# trinketm0fader_35mmad.net
KiCad netlist of a schematic drawn in EAGLE
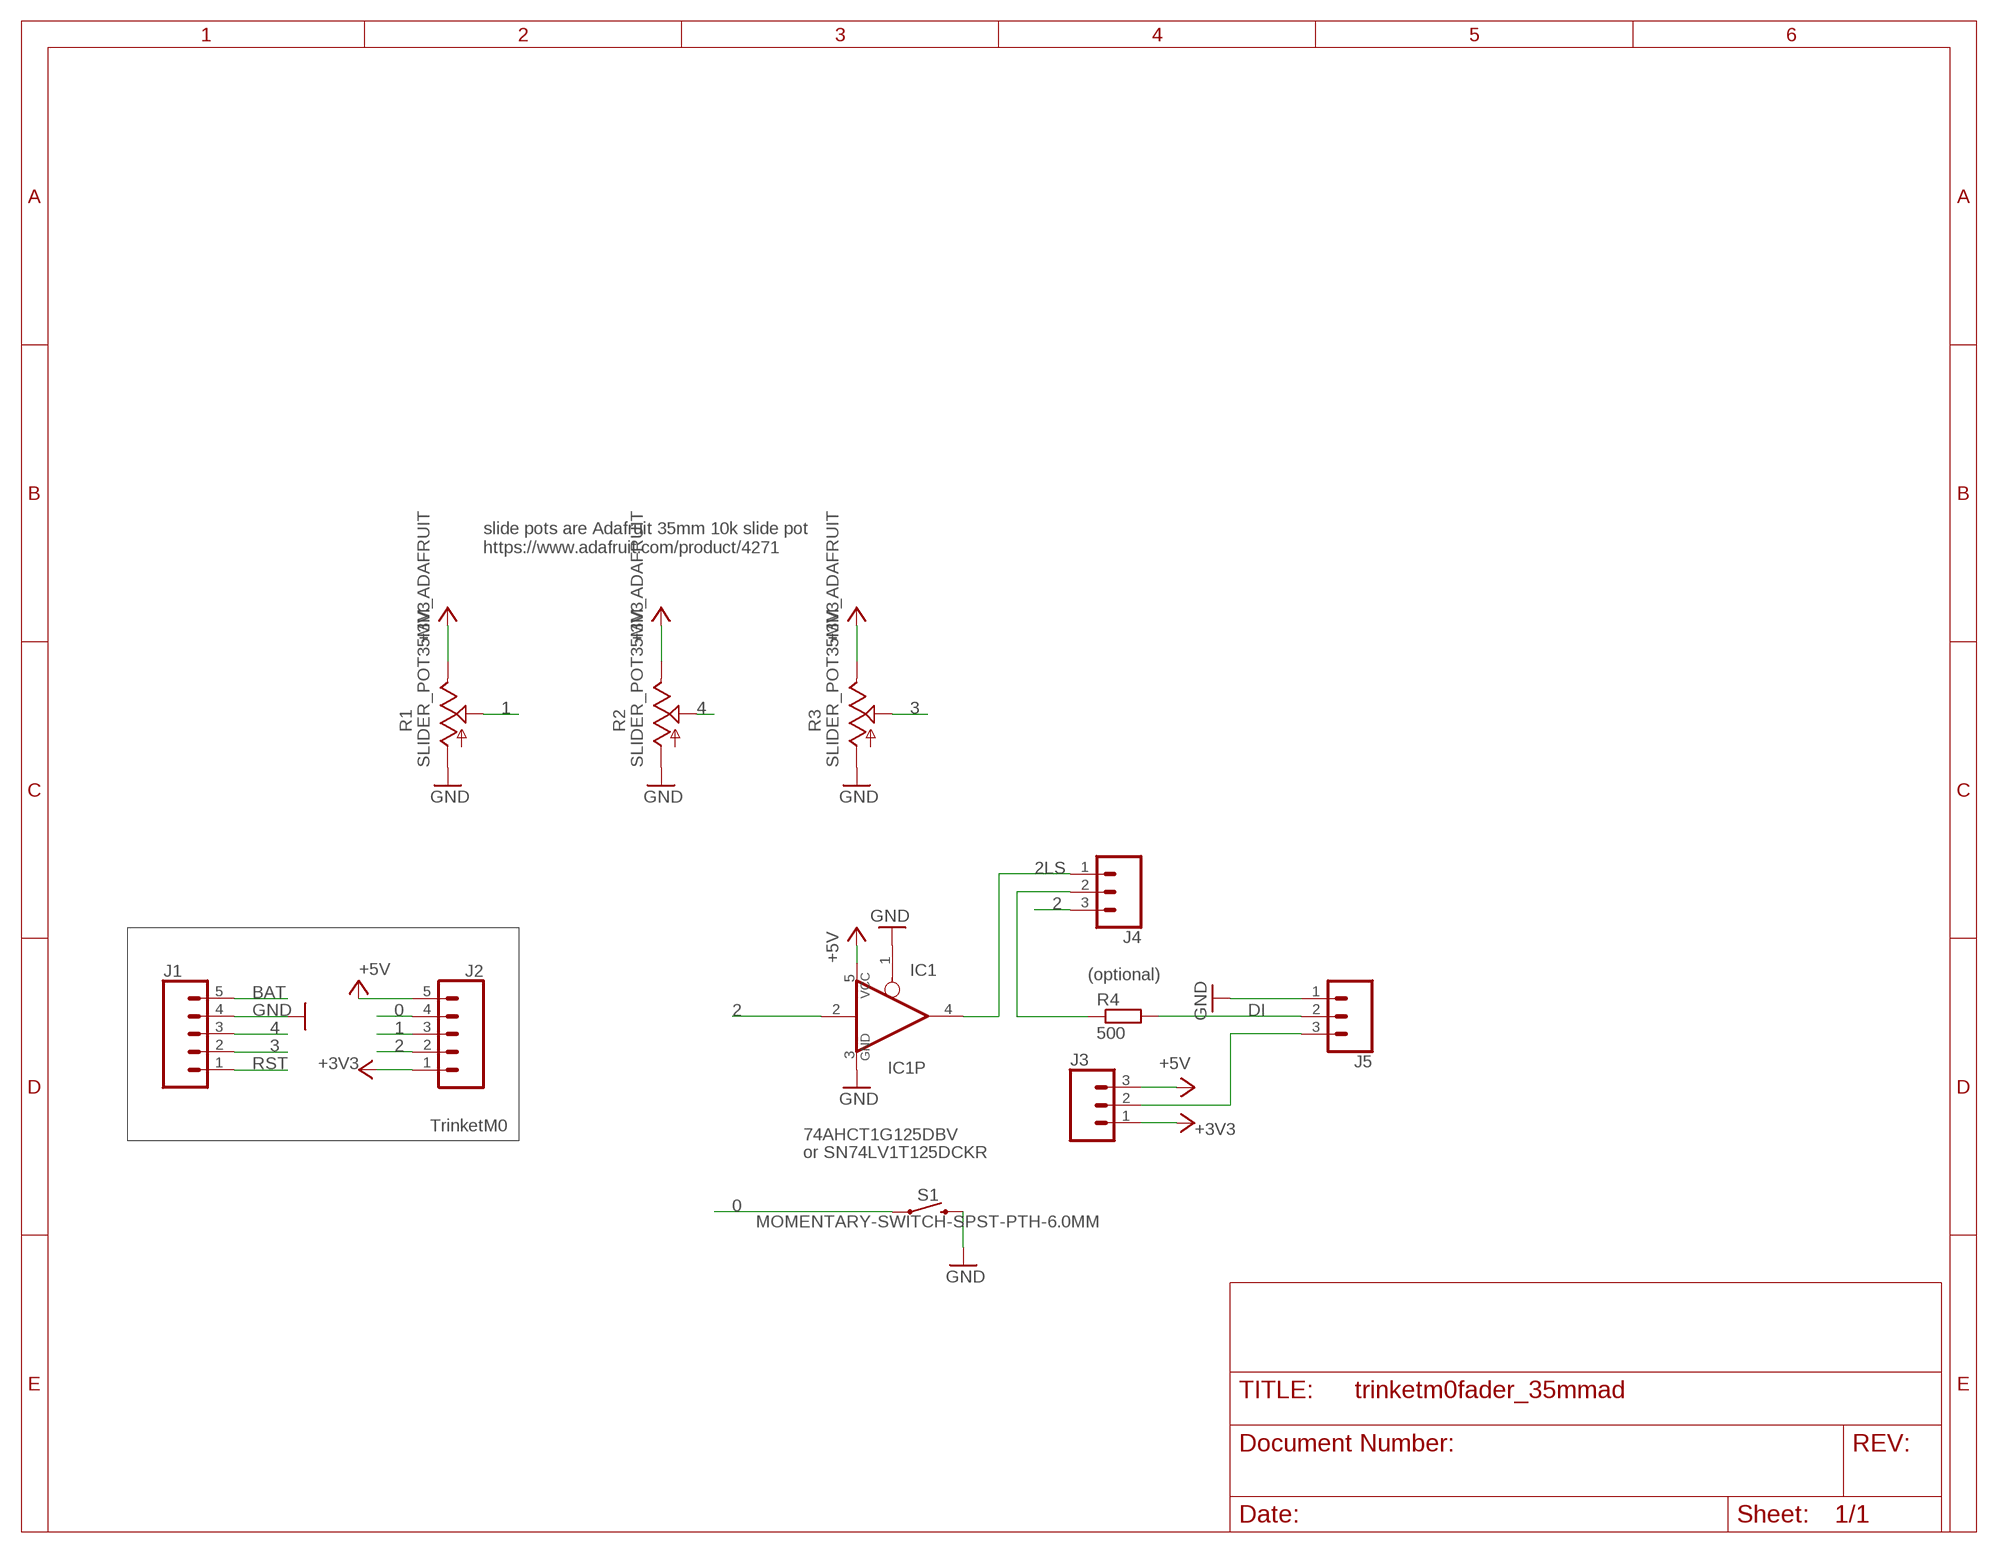
[diagram p0: schematic, sheet 1]

(export (version "E")
  (design (tool "Eeschema 10.0.6"))
  (components
    (comp (ref "IC1")
      (value "74AHCT1G125DBV")
      (footprint "eagle-import:SOT23-5")
      (libsource (lib "eagle-import") (part "741G125DBVAHCT"))
    )
    (comp (ref "J1")
      (value "CONN_05")
      (footprint "eagle-import:1X05")
      (libsource (lib "eagle-import") (part "CONN_05"))
    )
    (comp (ref "J2")
      (value "CONN_05")
      (footprint "eagle-import:1X05")
      (libsource (lib "eagle-import") (part "CONN_05"))
    )
    (comp (ref "J3")
      (value "CONN_03")
      (footprint "eagle-import:1X03")
      (libsource (lib "eagle-import") (part "CONN_03"))
    )
    (comp (ref "J4")
      (value "CONN_03")
      (footprint "eagle-import:1X03")
      (libsource (lib "eagle-import") (part "CONN_03"))
    )
    (comp (ref "J5")
      (value "CONN_03")
      (footprint "eagle-import:1X03")
      (libsource (lib "eagle-import") (part "CONN_03"))
    )
    (comp (ref "R1")
      (value "SLIDER_POT35MM_ADAFRUIT")
      (footprint "eagle-import:SLIDEPOD_35MM_ADAFRUIT")
      (libsource (lib "eagle-import") (part "SLIDER_POT35MM_ADAFRUIT"))
    )
    (comp (ref "R2")
      (value "SLIDER_POT35MM_ADAFRUIT")
      (footprint "eagle-import:SLIDEPOD_35MM_ADAFRUIT")
      (libsource (lib "eagle-import") (part "SLIDER_POT35MM_ADAFRUIT"))
    )
    (comp (ref "R3")
      (value "SLIDER_POT35MM_ADAFRUIT")
      (footprint "eagle-import:SLIDEPOD_35MM_ADAFRUIT")
      (libsource (lib "eagle-import") (part "SLIDER_POT35MM_ADAFRUIT"))
    )
    (comp (ref "R4")
      (value "500")
      (footprint "eagle-import:R0603")
      (libsource (lib "eagle-import") (part "R-EU_R0603"))
    )
    (comp (ref "S1")
      (value "MOMENTARY-SWITCH-SPST-PTH-6.0MM")
      (footprint "eagle-import:TACTILE_SWITCH_PTH_6.0MM")
      (libsource (lib "eagle-import") (part "MOMENTARY-SWITCH-SPST-PTH-6.0MM"))
    )
  )
  (nets
    (net (code "1") (name "+3V3") (class "Default")
      (node (ref "J2") (pin "1") (pinfunction "1_1") (pintype "passive"))
      (node (ref "J3") (pin "1") (pinfunction "1_1") (pintype "passive"))
      (node (ref "R1") (pin "P$1") (pinfunction "V_P$1") (pintype "passive"))
      (node (ref "R2") (pin "P$1") (pinfunction "V_P$1") (pintype "passive"))
      (node (ref "R3") (pin "P$1") (pinfunction "V_P$1") (pintype "passive"))
    )
    (net (code "2") (name "+5V") (class "Default")
      (node (ref "IC1") (pin "5") (pinfunction "VCC_5") (pintype "power_in"))
      (node (ref "J2") (pin "5") (pinfunction "5_5") (pintype "passive"))
      (node (ref "J3") (pin "3") (pinfunction "3_3") (pintype "passive"))
    )
    (net (code "3") (name "/0") (class "Default")
      (node (ref "J2") (pin "4") (pinfunction "4_4") (pintype "passive"))
      (node (ref "S1") (pin "1") (pinfunction "1_1") (pintype "passive"))
    )
    (net (code "4") (name "/1") (class "Default")
      (node (ref "J2") (pin "3") (pinfunction "3_3") (pintype "passive"))
      (node (ref "R1") (pin "P$2") (pinfunction "W_P$2") (pintype "passive"))
    )
    (net (code "5") (name "/2") (class "Default")
      (node (ref "IC1") (pin "2") (pinfunction "I_2") (pintype "input"))
      (node (ref "J2") (pin "2") (pinfunction "2_2") (pintype "passive"))
      (node (ref "J4") (pin "3") (pinfunction "3_3") (pintype "passive"))
    )
    (net (code "6") (name "/2LS") (class "Default")
      (node (ref "IC1") (pin "4") (pinfunction "O_4") (pintype "tri_state"))
      (node (ref "J4") (pin "1") (pinfunction "1_1") (pintype "passive"))
    )
    (net (code "7") (name "/3") (class "Default")
      (node (ref "J1") (pin "2") (pinfunction "2_2") (pintype "passive"))
      (node (ref "R3") (pin "P$2") (pinfunction "W_P$2") (pintype "passive"))
    )
    (net (code "8") (name "/4") (class "Default")
      (node (ref "J1") (pin "3") (pinfunction "3_3") (pintype "passive"))
      (node (ref "R2") (pin "P$2") (pinfunction "W_P$2") (pintype "passive"))
    )
    (net (code "9") (name "/BAT") (class "Default")
      (node (ref "J1") (pin "5") (pinfunction "5_5") (pintype "passive"))
    )
    (net (code "10") (name "/DI") (class "Default")
      (node (ref "J5") (pin "2") (pinfunction "2_2") (pintype "passive"))
      (node (ref "R4") (pin "2") (pinfunction "2_2") (pintype "passive"))
    )
    (net (code "11") (name "/RST") (class "Default")
      (node (ref "J1") (pin "1") (pinfunction "1_1") (pintype "passive"))
    )
    (net (code "12") (name "GND") (class "Default")
      (node (ref "IC1") (pin "1") (pinfunction "OE_1") (pintype "input"))
      (node (ref "IC1") (pin "3") (pinfunction "GND_3") (pintype "power_in"))
      (node (ref "J1") (pin "4") (pinfunction "4_4") (pintype "passive"))
      (node (ref "J5") (pin "1") (pinfunction "1_1") (pintype "passive"))
      (node (ref "R1") (pin "P$3") (pinfunction "G_P$3") (pintype "passive"))
      (node (ref "R2") (pin "P$3") (pinfunction "G_P$3") (pintype "passive"))
      (node (ref "R3") (pin "P$3") (pinfunction "G_P$3") (pintype "passive"))
      (node (ref "S1") (pin "3") (pinfunction "2_3") (pintype "passive"))
    )
    (net (code "13") (name "Net-(J3-Pad2)") (class "Default")
      (node (ref "J3") (pin "2") (pinfunction "2_2") (pintype "passive"))
      (node (ref "J5") (pin "3") (pinfunction "3_3") (pintype "passive"))
    )
    (net (code "14") (name "Net-(J4-Pad2)") (class "Default")
      (node (ref "J4") (pin "2") (pinfunction "2_2") (pintype "passive"))
      (node (ref "R4") (pin "1") (pinfunction "1_1") (pintype "passive"))
    )
  )
)
